# ESP32.net
KiCad netlist of a schematic drawn in Altium Designer
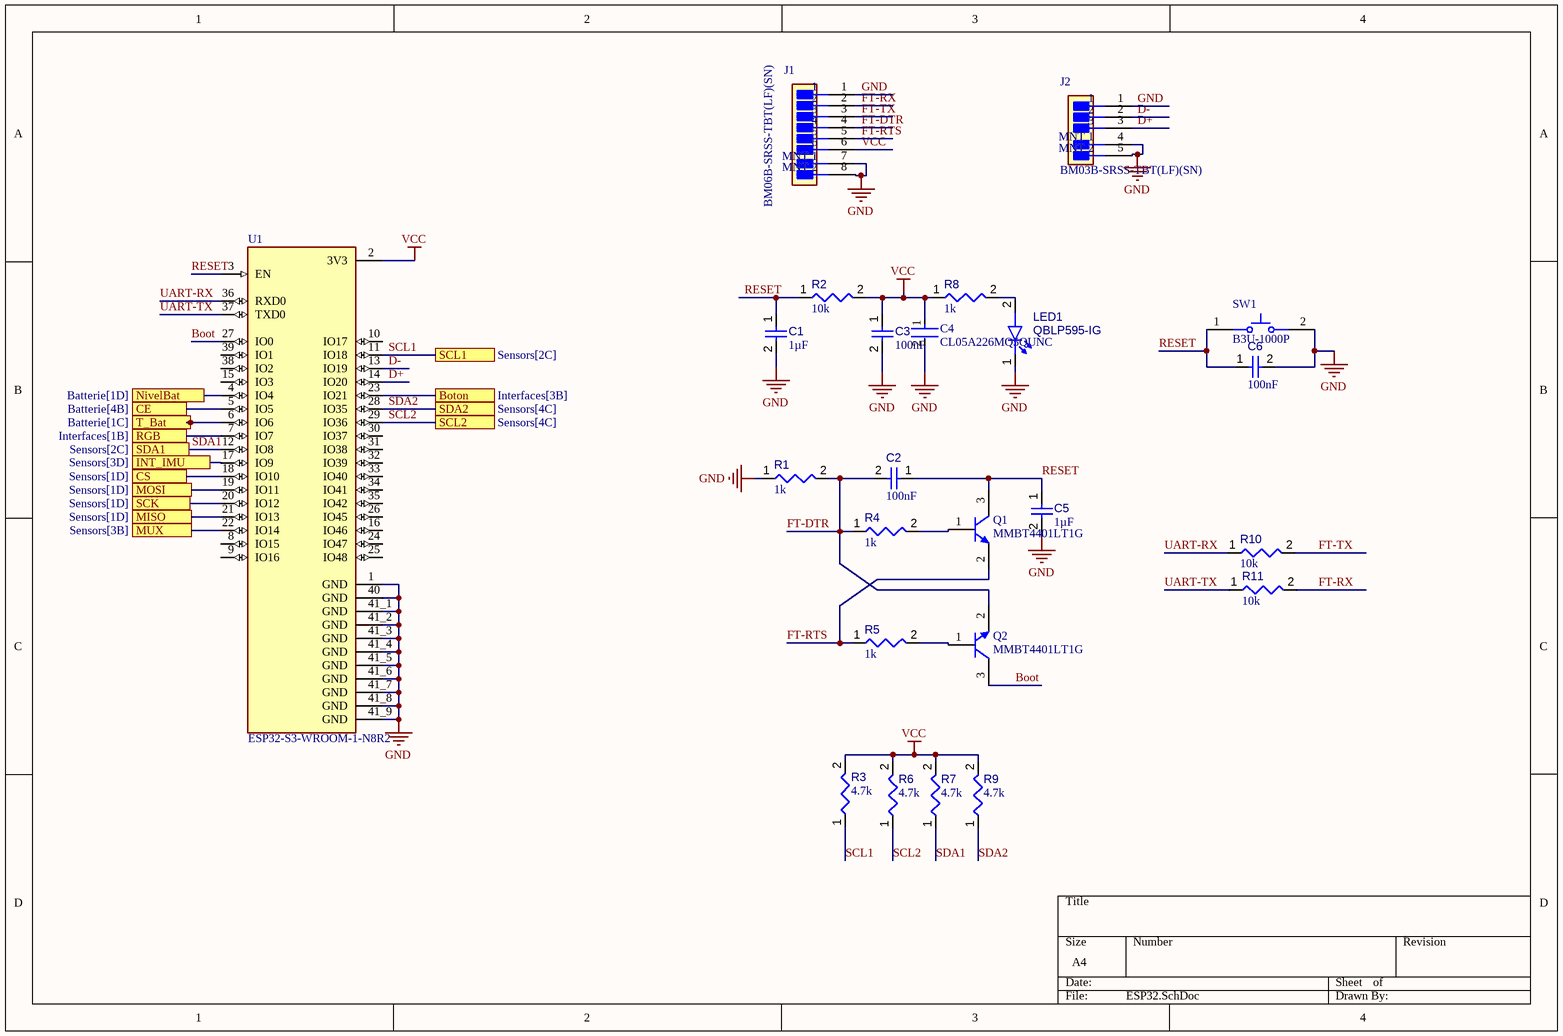
[diagram p0: ESP32.SchDoc]

(export (version "E")
  (design (tool "Eeschema 10.0.6"))
  (components
    (comp (ref "C1")
      (value "1µF")
      (footprint "CAPC1005X55X25LL05T10")
      (description "Chip Capacitor, 1 uF, +/- 10%, 6.3 V, 0402 (1005 Metric)")
      (fields (field (name "TOLERANCE") "10%") (field (name "Comment") "Capacitor 1 uF +/- 10% 6.3 V 0402"))
      (libsource (lib "Own Worskpace") (part "CAP-NP-2"))
    )
    (comp (ref "C2")
      (value "100nF")
      (footprint "CAPC1005X56X25LL10T15")
      (description "Chip Capacitor, 0.1 uF, +/- 5%, 16 V, 0402 (1005 Metric)")
      (fields (field (name "TOLERANCE") "5%") (field (name "Comment") "Capacitor 0.1 uF +/- 5% 16 V 0402"))
      (libsource (lib "Own Worskpace") (part "CAP-NP-2"))
    )
    (comp (ref "C3")
      (value "100nF")
      (footprint "CAPC1005X56X25LL10T15")
      (description "Chip Capacitor, 0.1 uF, +/- 5%, 16 V, 0402 (1005 Metric)")
      (fields (field (name "TOLERANCE") "5%") (field (name "Comment") "Capacitor 0.1 uF +/- 5% 16 V 0402"))
      (libsource (lib "Own Worskpace") (part "CAP-NP-2"))
    )
    (comp (ref "C4")
      (value "CL05A226MQ5QUNC")
      (footprint "FP-CL746-IPC_C")
      (description "Cap Ceramic 22uF 6.3V X5R ±20% SMD 0402 +85°C Paper T/R")
      (fields (field (name "TOLERANCE") "20%"))
      (libsource (lib "Altium Content Vault") (part "b4654b650e69147ec39a6b967a45e02"))
    )
    (comp (ref "C5")
      (value "1µF")
      (footprint "CAPC1005X55X25LL05T10")
      (description "Chip Capacitor, 1 uF, +/- 10%, 6.3 V, 0402 (1005 Metric)")
      (fields (field (name "TOLERANCE") "10%") (field (name "Comment") "Capacitor 1 uF +/- 10% 6.3 V 0402"))
      (libsource (lib "Own Worskpace") (part "CAP-NP-2"))
    )
    (comp (ref "C6")
      (value "100nF")
      (footprint "CAPC1005X56X25LL10T15")
      (description "Chip Capacitor, 0.1 uF, +/- 5%, 16 V, 0402 (1005 Metric)")
      (fields (field (name "TOLERANCE") "5%") (field (name "Comment") "Capacitor 0.1 uF +/- 5% 16 V 0402"))
      (libsource (lib "Own Worskpace") (part "CAP-NP-2"))
    )
    (comp (ref "J1")
      (value "BM06B-SRSS-TBT(LF)(SN)")
      (footprint "FP-BM06B-SRSS-TBT_LF_SN-MFG")
      (description "Conn Shrouded Header HDR 6 POS 1mm Solder ST SMD Embossed T/R")
      (libsource (lib "Own Worskpace") (part "ed24c53d9ba001d1a2a686240a95171"))
    )
    (comp (ref "J2")
      (value "BM03B-SRSS-TBT(LF)(SN)")
      (footprint "FP-BM03B-SRSS-TBT_LF_SN-MFG")
      (description "Conn Shrouded Header (4 Sides) HDR 3 POS 1mm Solder ST Top Entry SMD T/R")
      (libsource (lib "Own Worskpace") (part "49575d61908034f7a5505a4f8bf3aa4"))
    )
    (comp (ref "LED1")
      (value "QBLP595-IG")
      (footprint "QTB-QBLP595_V")
      (description "Chip LED 0402, Green, 0.02 A, 3.1 to 3.7 V, -40 to 80 degC, 2-Pin SMD, RoHS, Tape and Reel")
      (libsource (lib "Own Worskpace") (part "LED-KA-2"))
    )
    (comp (ref "Q1")
      (value "MMBT4401LT1G")
      (footprint "ONSC-SOT-23-3-318-08_V")
      (description "Switching Transistor, NPN Silicon, 3-Pin SOT-23, Pb-Free, Tape and Reel")
      (fields (field (name "MANUFACTURER") "On Semiconductor"))
      (libsource (lib "Altium Content Vault") (part "ONSC-NPN-B1E2C3-3"))
    )
    (comp (ref "Q2")
      (value "MMBT4401LT1G")
      (footprint "ONSC-SOT-23-3-318-08_V")
      (description "Switching Transistor, NPN Silicon, 3-Pin SOT-23, Pb-Free, Tape and Reel")
      (fields (field (name "MANUFACTURER") "On Semiconductor"))
      (libsource (lib "Altium Content Vault") (part "ONSC-NPN-B1E2C3-3"))
    )
    (comp (ref "R1")
      (value "1k")
      (footprint "RESC0402(1005)_L")
      (description "Chip Resistor, 1 kOhms, +/-5 %, 63 mW, -55 to 155 degC, 0402")
      (fields (field (name "TOLERANCE") "5%") (field (name "POWER") "63mW"))
      (libsource (lib "Own Worskpace") (part "RES-2"))
    )
    (comp (ref "R2")
      (value "10k")
      (footprint "RESC0402(1005)_L")
      (description "Chip Resistor, 10 kOhms, +/-1 %, 63 mW, -55 to 125 degC, 0402")
      (fields (field (name "POWER") "63mW") (field (name "TOLERANCE") "1%"))
      (libsource (lib "Own Worskpace") (part "RES-2"))
    )
    (comp (ref "R3")
      (value "4.7k")
      (footprint "RESC1005X40X25ML05T05")
      (description "Chip Resistor, 4.7 KOhm, +/- 1%, 0.1 W, -55 to 155 degC, 0402 (1005 Metric)")
      (fields (field (name "POWER") "100mW") (field (name "TOLERANCE") "1%"))
      (libsource (lib "Own Worskpace") (part "RES-2"))
    )
    (comp (ref "R4")
      (value "1k")
      (footprint "RESC0402(1005)_L")
      (description "Chip Resistor, 1 kOhms, +/-5 %, 63 mW, -55 to 155 degC, 0402")
      (fields (field (name "TOLERANCE") "5%") (field (name "POWER") "63mW"))
      (libsource (lib "Own Worskpace") (part "RES-2"))
    )
    (comp (ref "R5")
      (value "1k")
      (footprint "RESC0402(1005)_L")
      (description "Chip Resistor, 1 kOhms, +/-5 %, 63 mW, -55 to 155 degC, 0402")
      (fields (field (name "TOLERANCE") "5%") (field (name "POWER") "63mW"))
      (libsource (lib "Own Worskpace") (part "RES-2"))
    )
    (comp (ref "R6")
      (value "4.7k")
      (footprint "RESC1005X40X25ML05T05")
      (description "Chip Resistor, 4.7 KOhm, +/- 1%, 0.1 W, -55 to 155 degC, 0402 (1005 Metric)")
      (fields (field (name "POWER") "100mW") (field (name "TOLERANCE") "1%"))
      (libsource (lib "Own Worskpace") (part "RES-2"))
    )
    (comp (ref "R7")
      (value "4.7k")
      (footprint "RESC1005X40X25ML05T05")
      (description "Chip Resistor, 4.7 KOhm, +/- 1%, 0.1 W, -55 to 155 degC, 0402 (1005 Metric)")
      (fields (field (name "POWER") "100mW") (field (name "TOLERANCE") "1%"))
      (libsource (lib "Own Worskpace") (part "RES-2"))
    )
    (comp (ref "R8")
      (value "1k")
      (footprint "RESC0402(1005)_L")
      (description "Chip Resistor, 1 kOhms, +/-5 %, 63 mW, -55 to 155 degC, 0402")
      (fields (field (name "TOLERANCE") "5%") (field (name "POWER") "63mW"))
      (libsource (lib "Own Worskpace") (part "RES-2"))
    )
    (comp (ref "R9")
      (value "4.7k")
      (footprint "RESC1005X40X25ML05T05")
      (description "Chip Resistor, 4.7 KOhm, +/- 1%, 0.1 W, -55 to 155 degC, 0402 (1005 Metric)")
      (fields (field (name "POWER") "100mW") (field (name "TOLERANCE") "1%"))
      (libsource (lib "Own Worskpace") (part "RES-2"))
    )
    (comp (ref "R10")
      (value "10k")
      (footprint "RESC0402(1005)_L")
      (description "Chip Resistor, 10 kOhms, +/-1 %, 63 mW, -55 to 125 degC, 0402")
      (fields (field (name "POWER") "63mW") (field (name "TOLERANCE") "1%"))
      (libsource (lib "Own Worskpace") (part "RES-2"))
    )
    (comp (ref "R11")
      (value "10k")
      (footprint "RESC0402(1005)_L")
      (description "Chip Resistor, 10 kOhms, +/-1 %, 63 mW, -55 to 125 degC, 0402")
      (fields (field (name "POWER") "63mW") (field (name "TOLERANCE") "1%"))
      (libsource (lib "Own Worskpace") (part "RES-2"))
    )
    (comp (ref "SW1")
      (value "B3U-1000P")
      (footprint "OMRON-B3U-1000_V")
      (description "Tactile Switch, SPST-NO, 0.05 A, 12 V, -25 to 70 degC, 2-Pin SMD, RoHS, Tape and Reel")
      (fields (field (name "MANUFACTURER") "Omron Electronic Components"))
      (libsource (lib "Own Worskpace") (part "SW-SPST-NO-2"))
    )
    (comp (ref "U1")
      (value "ESP32-S3-WROOM-1-N8R2")
      (footprint "XCVR_ESP32-S3-WROOM-1-N8R2")
      (description "WiFi 802.11a/b/g/n, Bluetooth v5.0 Transceiver Module 2.4GHz Antenna Not Included -")
      (fields (field (name "MF") "Espressif Systems"))
      (libsource (lib "Own Worskpace") (part "ESP32-S3-WROOM-1-N8R2"))
    )
  )
  (nets
    (net (code "1") (name "/Boot") (class "Default")
      (node (ref "Q2") (pin "3") (pinfunction "C_3") (pintype "passive"))
      (node (ref "U1") (pin "27") (pinfunction "IO0_27") (pintype "bidirectional"))
    )
    (net (code "2") (name "/Boton") (class "Default")
      (node (ref "U1") (pin "23") (pinfunction "IO21_23") (pintype "bidirectional"))
    )
    (net (code "3") (name "/CE") (class "Default")
      (node (ref "U1") (pin "5") (pinfunction "IO5_5") (pintype "bidirectional"))
    )
    (net (code "4") (name "/CS") (class "Default")
      (node (ref "U1") (pin "18") (pinfunction "IO10_18") (pintype "bidirectional"))
    )
    (net (code "5") (name "/D+") (class "Default")
      (node (ref "J2") (pin "3") (pinfunction "3_3") (pintype "passive"))
      (node (ref "U1") (pin "14") (pinfunction "IO20_14") (pintype "bidirectional"))
    )
    (net (code "6") (name "/D-") (class "Default")
      (node (ref "J2") (pin "2") (pinfunction "2_2") (pintype "passive"))
      (node (ref "U1") (pin "13") (pinfunction "IO19_13") (pintype "bidirectional"))
    )
    (net (code "7") (name "/FT-DTR") (class "Default")
      (node (ref "C2") (pin "2") (pinfunction "2_2") (pintype "passive"))
      (node (ref "J1") (pin "4") (pinfunction "4_4") (pintype "passive"))
      (node (ref "Q2") (pin "2") (pinfunction "E_2") (pintype "passive"))
      (node (ref "R1") (pin "2") (pinfunction "2_2") (pintype "passive"))
      (node (ref "R4") (pin "1") (pinfunction "1_1") (pintype "passive"))
    )
    (net (code "8") (name "/FT-RTS") (class "Default")
      (node (ref "J1") (pin "5") (pinfunction "5_5") (pintype "passive"))
      (node (ref "Q1") (pin "2") (pinfunction "E_2") (pintype "passive"))
      (node (ref "R5") (pin "1") (pinfunction "1_1") (pintype "passive"))
    )
    (net (code "9") (name "/FT-RX") (class "Default")
      (node (ref "J1") (pin "2") (pinfunction "2_2") (pintype "passive"))
      (node (ref "R11") (pin "2") (pinfunction "2_2") (pintype "passive"))
    )
    (net (code "10") (name "/FT-TX") (class "Default")
      (node (ref "J1") (pin "3") (pinfunction "3_3") (pintype "passive"))
      (node (ref "R10") (pin "2") (pinfunction "2_2") (pintype "passive"))
    )
    (net (code "11") (name "/INT_IMU") (class "Default")
      (node (ref "U1") (pin "17") (pinfunction "IO9_17") (pintype "bidirectional"))
    )
    (net (code "12") (name "/MISO") (class "Default")
      (node (ref "U1") (pin "21") (pinfunction "IO13_21") (pintype "bidirectional"))
    )
    (net (code "13") (name "/MOSI") (class "Default")
      (node (ref "U1") (pin "19") (pinfunction "IO11_19") (pintype "bidirectional"))
    )
    (net (code "14") (name "/MUX") (class "Default")
      (node (ref "U1") (pin "22") (pinfunction "IO14_22") (pintype "bidirectional"))
    )
    (net (code "15") (name "/NivelBat") (class "Default")
      (node (ref "U1") (pin "4") (pinfunction "IO4_4") (pintype "bidirectional"))
    )
    (net (code "16") (name "/RESET") (class "Default")
      (node (ref "C1") (pin "1") (pinfunction "1_1") (pintype "passive"))
      (node (ref "C2") (pin "1") (pinfunction "1_1") (pintype "passive"))
      (node (ref "C5") (pin "1") (pinfunction "1_1") (pintype "passive"))
      (node (ref "C6") (pin "1") (pinfunction "1_1") (pintype "passive"))
      (node (ref "Q1") (pin "3") (pinfunction "C_3") (pintype "passive"))
      (node (ref "R2") (pin "1") (pinfunction "1_1") (pintype "passive"))
      (node (ref "SW1") (pin "1") (pinfunction "1_1") (pintype "passive"))
      (node (ref "U1") (pin "3") (pinfunction "EN_3") (pintype "input"))
    )
    (net (code "17") (name "/RGB") (class "Default")
      (node (ref "U1") (pin "7") (pinfunction "IO7_7") (pintype "bidirectional"))
    )
    (net (code "18") (name "/SCK") (class "Default")
      (node (ref "U1") (pin "20") (pinfunction "IO12_20") (pintype "bidirectional"))
    )
    (net (code "19") (name "/SCL1") (class "Default")
      (node (ref "R3") (pin "1") (pinfunction "1_1") (pintype "passive"))
      (node (ref "U1") (pin "11") (pinfunction "IO18_11") (pintype "bidirectional"))
    )
    (net (code "20") (name "/SCL2") (class "Default")
      (node (ref "R6") (pin "1") (pinfunction "1_1") (pintype "passive"))
      (node (ref "U1") (pin "29") (pinfunction "IO36_29") (pintype "bidirectional"))
    )
    (net (code "21") (name "/SDA1") (class "Default")
      (node (ref "R7") (pin "1") (pinfunction "1_1") (pintype "passive"))
      (node (ref "U1") (pin "12") (pinfunction "IO8_12") (pintype "bidirectional"))
    )
    (net (code "22") (name "/SDA2") (class "Default")
      (node (ref "R9") (pin "1") (pinfunction "1_1") (pintype "passive"))
      (node (ref "U1") (pin "28") (pinfunction "IO35_28") (pintype "bidirectional"))
    )
    (net (code "23") (name "/T_Bat") (class "Default")
      (node (ref "U1") (pin "6") (pinfunction "IO6_6") (pintype "bidirectional"))
    )
    (net (code "24") (name "/UART-RX") (class "Default")
      (node (ref "R10") (pin "1") (pinfunction "1_1") (pintype "passive"))
      (node (ref "U1") (pin "36") (pinfunction "RXD0_36") (pintype "bidirectional"))
    )
    (net (code "25") (name "/UART-TX") (class "Default")
      (node (ref "R11") (pin "1") (pinfunction "1_1") (pintype "passive"))
      (node (ref "U1") (pin "37") (pinfunction "TXD0_37") (pintype "bidirectional"))
    )
    (net (code "26") (name "GND") (class "Default")
      (node (ref "C1") (pin "2") (pinfunction "2_2") (pintype "passive"))
      (node (ref "C3") (pin "2") (pinfunction "2_2") (pintype "passive"))
      (node (ref "C4") (pin "2") (pinfunction "2_2") (pintype "passive"))
      (node (ref "C5") (pin "2") (pinfunction "2_2") (pintype "passive"))
      (node (ref "C6") (pin "2") (pinfunction "2_2") (pintype "passive"))
      (node (ref "J1") (pin "1") (pinfunction "1_1") (pintype "passive"))
      (node (ref "J1") (pin "7") (pinfunction "MNT_1_7") (pintype "passive"))
      (node (ref "J1") (pin "8") (pinfunction "MNT_2_8") (pintype "passive"))
      (node (ref "J2") (pin "1") (pinfunction "1_1") (pintype "passive"))
      (node (ref "J2") (pin "4") (pinfunction "MNT_1_4") (pintype "passive"))
      (node (ref "J2") (pin "5") (pinfunction "MNT_2_5") (pintype "passive"))
      (node (ref "LED1") (pin "1") (pinfunction "K_1") (pintype "passive"))
      (node (ref "R1") (pin "1") (pinfunction "1_1") (pintype "passive"))
      (node (ref "SW1") (pin "2") (pinfunction "2_2") (pintype "passive"))
      (node (ref "U1") (pin "1") (pinfunction "GND_1") (pintype "power_in"))
      (node (ref "U1") (pin "40") (pinfunction "GND_40") (pintype "power_in"))
      (node (ref "U1") (pin "41_1") (pinfunction "GND_41_1") (pintype "power_in"))
      (node (ref "U1") (pin "41_2") (pinfunction "GND_41_2") (pintype "power_in"))
      (node (ref "U1") (pin "41_3") (pinfunction "GND_41_3") (pintype "power_in"))
      (node (ref "U1") (pin "41_4") (pinfunction "GND_41_4") (pintype "power_in"))
      (node (ref "U1") (pin "41_5") (pinfunction "GND_41_5") (pintype "power_in"))
      (node (ref "U1") (pin "41_6") (pinfunction "GND_41_6") (pintype "power_in"))
      (node (ref "U1") (pin "41_7") (pinfunction "GND_41_7") (pintype "power_in"))
      (node (ref "U1") (pin "41_8") (pinfunction "GND_41_8") (pintype "power_in"))
      (node (ref "U1") (pin "41_9") (pinfunction "GND_41_9") (pintype "power_in"))
    )
    (net (code "27") (name "Net-(LED1-A)") (class "Default")
      (node (ref "LED1") (pin "2") (pinfunction "A_2") (pintype "passive"))
      (node (ref "R8") (pin "2") (pinfunction "2_2") (pintype "passive"))
    )
    (net (code "28") (name "Net-(Q1-B)") (class "Default")
      (node (ref "Q1") (pin "1") (pinfunction "B_1") (pintype "passive"))
      (node (ref "R4") (pin "2") (pinfunction "2_2") (pintype "passive"))
    )
    (net (code "29") (name "Net-(Q2-B)") (class "Default")
      (node (ref "Q2") (pin "1") (pinfunction "B_1") (pintype "passive"))
      (node (ref "R5") (pin "2") (pinfunction "2_2") (pintype "passive"))
    )
    (net (code "30") (name "VCC") (class "Default")
      (node (ref "C3") (pin "1") (pinfunction "1_1") (pintype "passive"))
      (node (ref "C4") (pin "1") (pinfunction "1_1") (pintype "passive"))
      (node (ref "J1") (pin "6") (pinfunction "6_6") (pintype "passive"))
      (node (ref "R2") (pin "2") (pinfunction "2_2") (pintype "passive"))
      (node (ref "R3") (pin "2") (pinfunction "2_2") (pintype "passive"))
      (node (ref "R6") (pin "2") (pinfunction "2_2") (pintype "passive"))
      (node (ref "R7") (pin "2") (pinfunction "2_2") (pintype "passive"))
      (node (ref "R8") (pin "1") (pinfunction "1_1") (pintype "passive"))
      (node (ref "R9") (pin "2") (pinfunction "2_2") (pintype "passive"))
      (node (ref "U1") (pin "2") (pinfunction "3V3_2") (pintype "power_in"))
    )
    (net (code "31") (name "unconnected-(U1-IO1-Pad39)") (class "Default")
      (node (ref "U1") (pin "39") (pinfunction "IO1_39") (pintype "bidirectional"))
    )
    (net (code "32") (name "unconnected-(U1-IO2-Pad38)") (class "Default")
      (node (ref "U1") (pin "38") (pinfunction "IO2_38") (pintype "bidirectional"))
    )
    (net (code "33") (name "unconnected-(U1-IO3-Pad15)") (class "Default")
      (node (ref "U1") (pin "15") (pinfunction "IO3_15") (pintype "bidirectional"))
    )
    (net (code "34") (name "unconnected-(U1-IO15-Pad8)") (class "Default")
      (node (ref "U1") (pin "8") (pinfunction "IO15_8") (pintype "bidirectional"))
    )
    (net (code "35") (name "unconnected-(U1-IO16-Pad9)") (class "Default")
      (node (ref "U1") (pin "9") (pinfunction "IO16_9") (pintype "bidirectional"))
    )
    (net (code "36") (name "unconnected-(U1-IO17-Pad10)") (class "Default")
      (node (ref "U1") (pin "10") (pinfunction "IO17_10") (pintype "bidirectional"))
    )
    (net (code "37") (name "unconnected-(U1-IO37-Pad30)") (class "Default")
      (node (ref "U1") (pin "30") (pinfunction "IO37_30") (pintype "bidirectional"))
    )
    (net (code "38") (name "unconnected-(U1-IO38-Pad31)") (class "Default")
      (node (ref "U1") (pin "31") (pinfunction "IO38_31") (pintype "bidirectional"))
    )
    (net (code "39") (name "unconnected-(U1-IO39-Pad32)") (class "Default")
      (node (ref "U1") (pin "32") (pinfunction "IO39_32") (pintype "bidirectional"))
    )
    (net (code "40") (name "unconnected-(U1-IO40-Pad33)") (class "Default")
      (node (ref "U1") (pin "33") (pinfunction "IO40_33") (pintype "bidirectional"))
    )
    (net (code "41") (name "unconnected-(U1-IO41-Pad34)") (class "Default")
      (node (ref "U1") (pin "34") (pinfunction "IO41_34") (pintype "bidirectional"))
    )
    (net (code "42") (name "unconnected-(U1-IO42-Pad35)") (class "Default")
      (node (ref "U1") (pin "35") (pinfunction "IO42_35") (pintype "bidirectional"))
    )
    (net (code "43") (name "unconnected-(U1-IO45-Pad26)") (class "Default")
      (node (ref "U1") (pin "26") (pinfunction "IO45_26") (pintype "bidirectional"))
    )
    (net (code "44") (name "unconnected-(U1-IO46-Pad16)") (class "Default")
      (node (ref "U1") (pin "16") (pinfunction "IO46_16") (pintype "bidirectional"))
    )
    (net (code "45") (name "unconnected-(U1-IO47-Pad24)") (class "Default")
      (node (ref "U1") (pin "24") (pinfunction "IO47_24") (pintype "bidirectional"))
    )
    (net (code "46") (name "unconnected-(U1-IO48-Pad25)") (class "Default")
      (node (ref "U1") (pin "25") (pinfunction "IO48_25") (pintype "bidirectional"))
    )
  )
)
